# Signal_Protection.net
KiCad netlist of a schematic drawn in Altium Designer
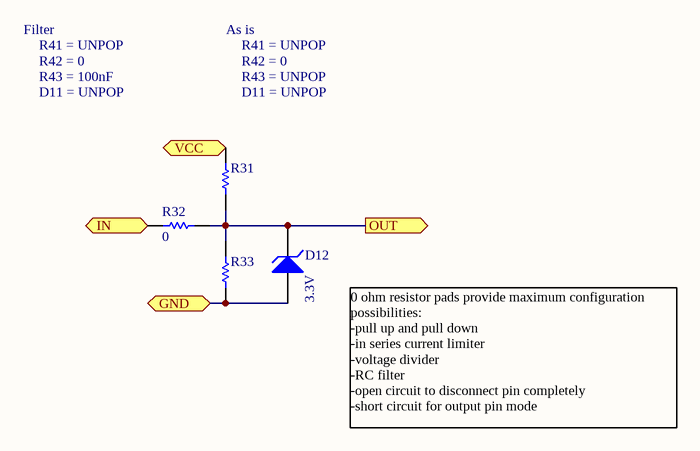
[diagram p0: Signal_Protection.SchDoc]

(export (version "E")
  (design (tool "Eeschema 10.0.6"))
  (components
    (comp (ref "D12")
      (value "DS - TVS ESD5Z3.3T1G")
      (footprint "DS-SOD523")
      (description "TVS 3.3V")
      (fields
        (field (name "MANUFACTURER") "ON Semiconductor")
        (field (name "VOLTAGE - REVERSE STANDOFF (TYP)") "3.3V")
      )
      (libsource (lib "CHINOOK_LIBRARY") (part "DS - TVS ESD5Z3.3T1G"))
    )
    (comp (ref "R31")
      (value "RS - RESISTOR")
      (footprint "RS-0603")
      (fields (field (name "TOLERANCE") "RES TOL") (field (name "POWER") "RES POWER"))
      (libsource (lib "CHINOOK_LIBRARY") (part "RS - RESISTOR"))
    )
    (comp (ref "R32")
      (value "0")
      (footprint "RS-0603")
      (fields
        (field (name "TOLERANCE") "RES TOL")
        (field (name "POWER") "RES POWER")
        (field (name "Comment") "RS - RESISTOR")
      )
      (libsource (lib "CHINOOK_LIBRARY") (part "RS - RESISTOR"))
    )
    (comp (ref "R33")
      (value "RS - RESISTOR")
      (footprint "RS-0603")
      (fields (field (name "TOLERANCE") "RES TOL") (field (name "POWER") "RES POWER"))
      (libsource (lib "CHINOOK_LIBRARY") (part "RS - RESISTOR"))
    )
  )
  (nets
    (net (code "1") (name "/GND") (class "Default")
      (node (ref "D12") (pin "A") (pinfunction "A_A") (pintype "passive"))
      (node (ref "R33") (pin "1") (pinfunction "1_1") (pintype "passive"))
    )
    (net (code "2") (name "/IN") (class "Default")
      (node (ref "R32") (pin "2") (pinfunction "2_2") (pintype "passive"))
    )
    (net (code "3") (name "/OUT") (class "Default")
      (node (ref "D12") (pin "K") (pinfunction "K_K") (pintype "passive"))
      (node (ref "R31") (pin "2") (pinfunction "2_2") (pintype "passive"))
      (node (ref "R32") (pin "1") (pinfunction "1_1") (pintype "passive"))
      (node (ref "R33") (pin "2") (pinfunction "2_2") (pintype "passive"))
    )
    (net (code "4") (name "/VCC") (class "Default")
      (node (ref "R31") (pin "1") (pinfunction "1_1") (pintype "passive"))
    )
  )
)
